# zxuno_v41.net
KiCad netlist of a schematic drawn in EAGLE
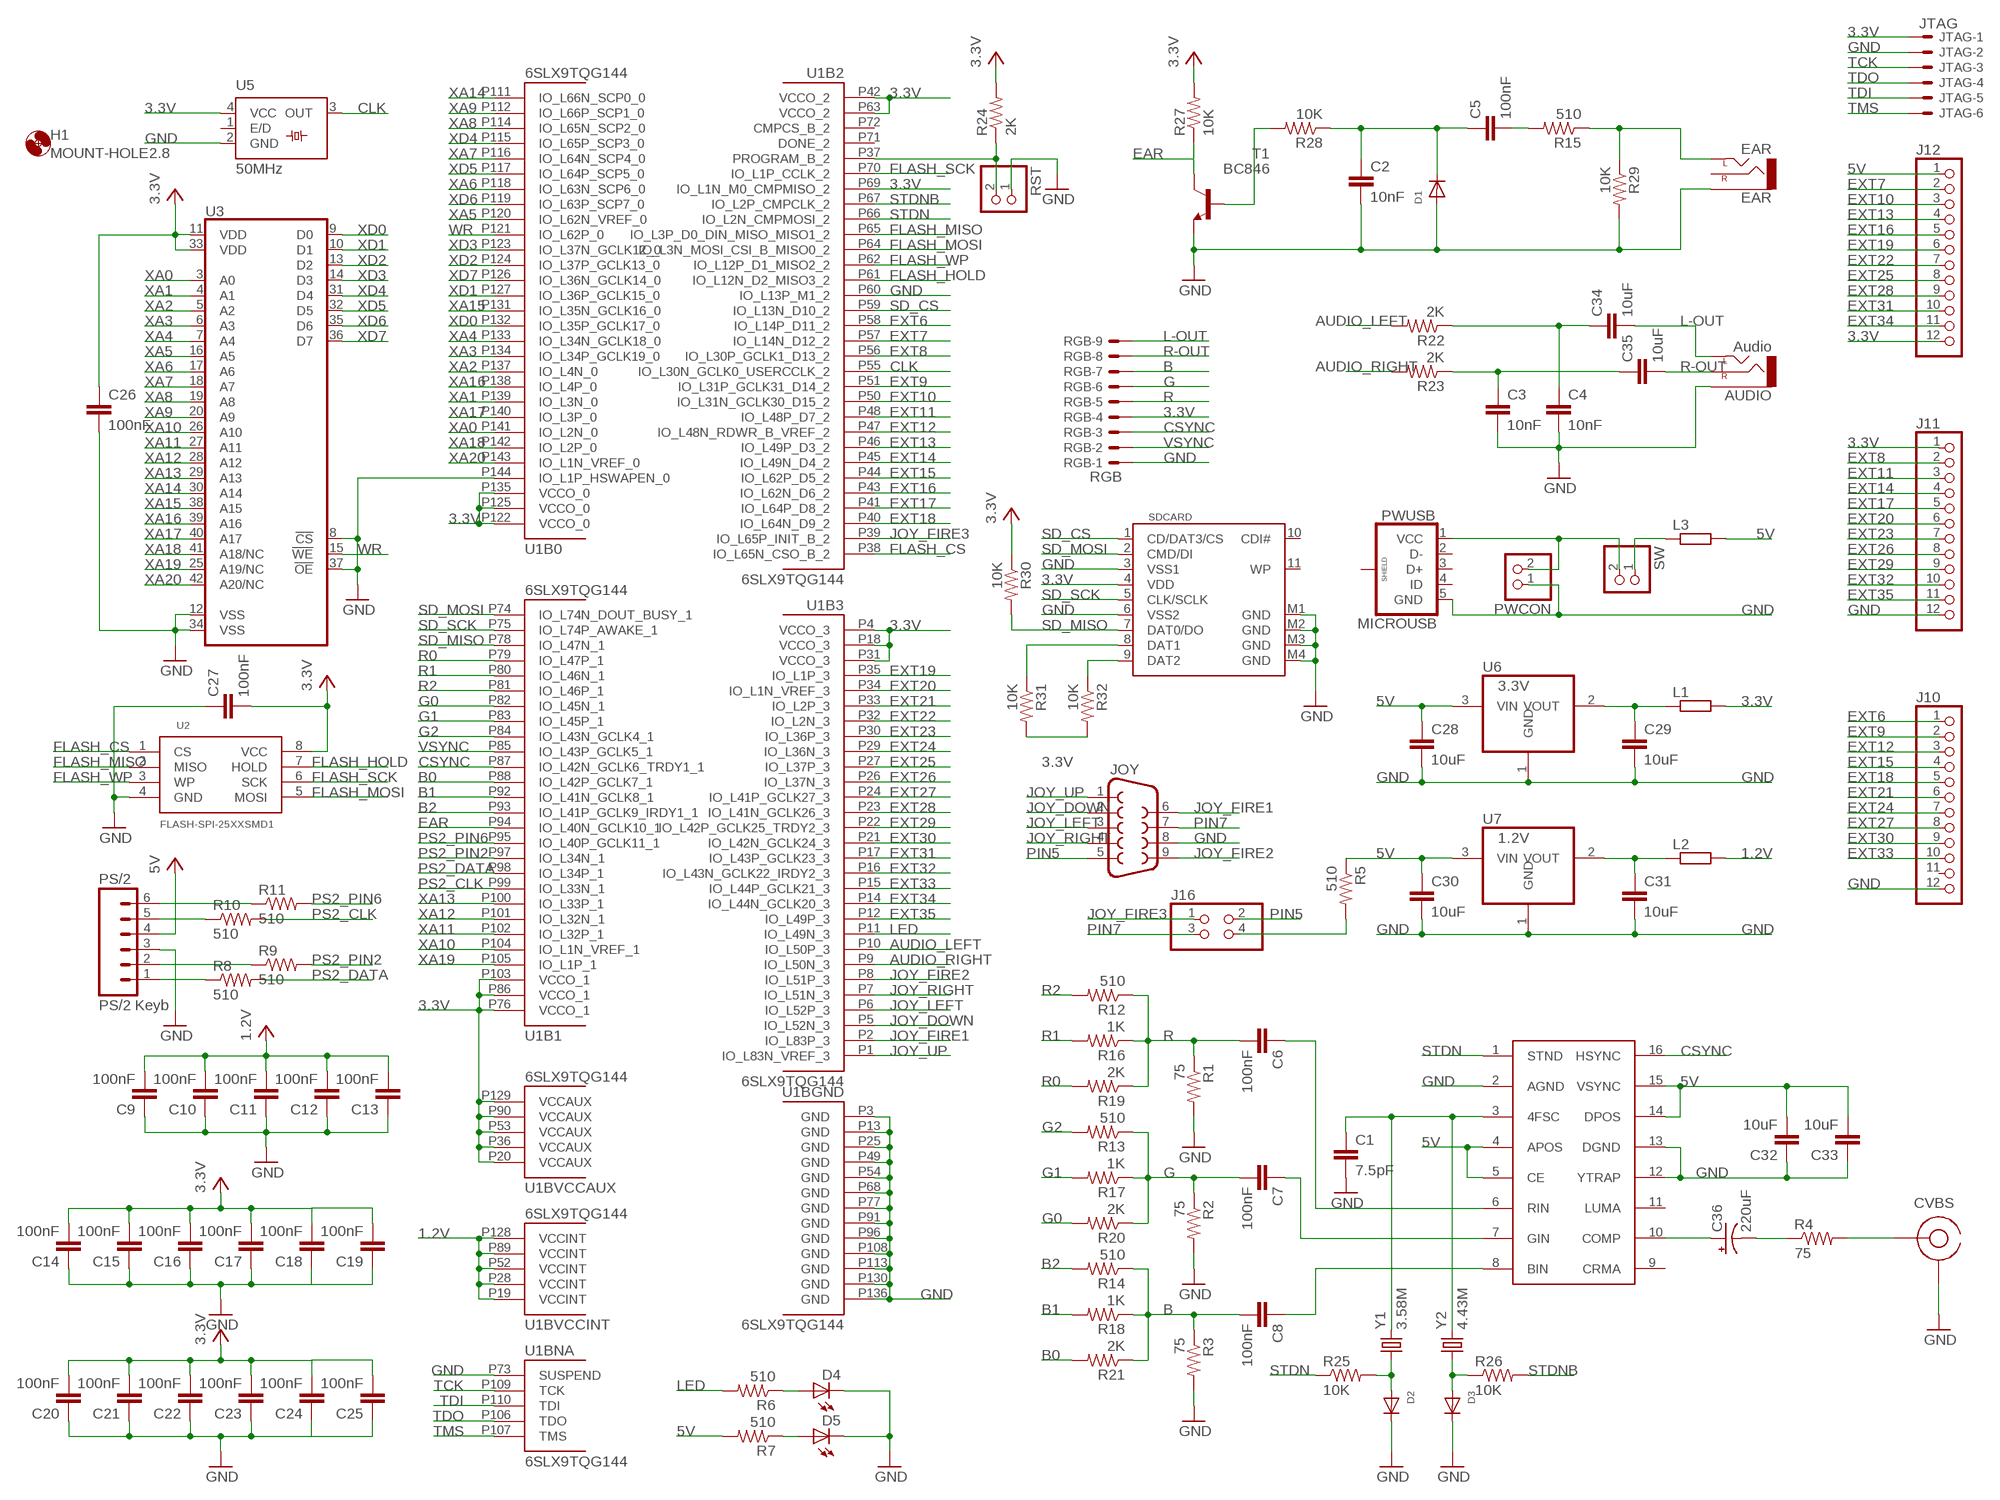
[diagram p0: schematic, sheet 1]

(export (version "E")
  (design (tool "Eeschema 10.0.6"))
  (components
    (comp (ref "AUDIO")
      (value "Audio")
      (footprint "eagle-import:AUDIO-JACK")
      (libsource (lib "eagle-import") (part "AUDIO-JACKPTH"))
    )
    (comp (ref "C1")
      (value "7.5pF")
      (footprint "eagle-import:C0805")
      (libsource (lib "eagle-import") (part "C-EUC0805"))
    )
    (comp (ref "C2")
      (value "10nF")
      (footprint "eagle-import:C0805")
      (libsource (lib "eagle-import") (part "C-EUC0805"))
    )
    (comp (ref "C3")
      (value "10nF")
      (footprint "eagle-import:C0805")
      (libsource (lib "eagle-import") (part "C-EUC0805"))
    )
    (comp (ref "C4")
      (value "10nF")
      (footprint "eagle-import:C0805")
      (libsource (lib "eagle-import") (part "C-EUC0805"))
    )
    (comp (ref "C5")
      (value "100nF")
      (footprint "eagle-import:C0603")
      (libsource (lib "eagle-import") (part "C-EUC0603"))
    )
    (comp (ref "C6")
      (value "100nF")
      (footprint "eagle-import:C0603")
      (libsource (lib "eagle-import") (part "C-EUC0603"))
    )
    (comp (ref "C7")
      (value "100nF")
      (footprint "eagle-import:C0603")
      (libsource (lib "eagle-import") (part "C-EUC0603"))
    )
    (comp (ref "C8")
      (value "100nF")
      (footprint "eagle-import:C0603")
      (libsource (lib "eagle-import") (part "C-EUC0603"))
    )
    (comp (ref "C9")
      (value "100nF")
      (footprint "eagle-import:C0603")
      (libsource (lib "eagle-import") (part "C-EUC0603"))
    )
    (comp (ref "C10")
      (value "100nF")
      (footprint "eagle-import:C0603")
      (libsource (lib "eagle-import") (part "C-EUC0603"))
    )
    (comp (ref "C11")
      (value "100nF")
      (footprint "eagle-import:C0603")
      (libsource (lib "eagle-import") (part "C-EUC0603"))
    )
    (comp (ref "C12")
      (value "100nF")
      (footprint "eagle-import:C0603")
      (libsource (lib "eagle-import") (part "C-EUC0603"))
    )
    (comp (ref "C13")
      (value "100nF")
      (footprint "eagle-import:C0603")
      (libsource (lib "eagle-import") (part "C-EUC0603"))
    )
    (comp (ref "C14")
      (value "100nF")
      (footprint "eagle-import:C0603")
      (libsource (lib "eagle-import") (part "C-EUC0603"))
    )
    (comp (ref "C15")
      (value "100nF")
      (footprint "eagle-import:C0603")
      (libsource (lib "eagle-import") (part "C-EUC0603"))
    )
    (comp (ref "C16")
      (value "100nF")
      (footprint "eagle-import:C0603")
      (libsource (lib "eagle-import") (part "C-EUC0603"))
    )
    (comp (ref "C17")
      (value "100nF")
      (footprint "eagle-import:C0603")
      (libsource (lib "eagle-import") (part "C-EUC0603"))
    )
    (comp (ref "C18")
      (value "100nF")
      (footprint "eagle-import:C0603")
      (libsource (lib "eagle-import") (part "C-EUC0603"))
    )
    (comp (ref "C19")
      (value "100nF")
      (footprint "eagle-import:C0603")
      (libsource (lib "eagle-import") (part "C-EUC0603"))
    )
    (comp (ref "C20")
      (value "100nF")
      (footprint "eagle-import:C0603")
      (libsource (lib "eagle-import") (part "C-EUC0603"))
    )
    (comp (ref "C21")
      (value "100nF")
      (footprint "eagle-import:C0603")
      (libsource (lib "eagle-import") (part "C-EUC0603"))
    )
    (comp (ref "C22")
      (value "100nF")
      (footprint "eagle-import:C0603")
      (libsource (lib "eagle-import") (part "C-EUC0603"))
    )
    (comp (ref "C23")
      (value "100nF")
      (footprint "eagle-import:C0603")
      (libsource (lib "eagle-import") (part "C-EUC0603"))
    )
    (comp (ref "C24")
      (value "100nF")
      (footprint "eagle-import:C0603")
      (libsource (lib "eagle-import") (part "C-EUC0603"))
    )
    (comp (ref "C25")
      (value "100nF")
      (footprint "eagle-import:C0603")
      (libsource (lib "eagle-import") (part "C-EUC0603"))
    )
    (comp (ref "C26")
      (value "100nF")
      (footprint "eagle-import:C0603")
      (libsource (lib "eagle-import") (part "C-EUC0603"))
    )
    (comp (ref "C27")
      (value "100nF")
      (footprint "eagle-import:C0603")
      (libsource (lib "eagle-import") (part "C-EUC0603"))
    )
    (comp (ref "C28")
      (value "10uF")
      (footprint "eagle-import:C0805")
      (libsource (lib "eagle-import") (part "C-EUC0805"))
    )
    (comp (ref "C29")
      (value "10uF")
      (footprint "eagle-import:C0805")
      (libsource (lib "eagle-import") (part "C-EUC0805"))
    )
    (comp (ref "C30")
      (value "10uF")
      (footprint "eagle-import:C0805")
      (libsource (lib "eagle-import") (part "C-EUC0805"))
    )
    (comp (ref "C31")
      (value "10uF")
      (footprint "eagle-import:C0805")
      (libsource (lib "eagle-import") (part "C-EUC0805"))
    )
    (comp (ref "C32")
      (value "10uF")
      (footprint "eagle-import:C0805")
      (libsource (lib "eagle-import") (part "C-EUC0805"))
    )
    (comp (ref "C33")
      (value "10uF")
      (footprint "eagle-import:C0805")
      (libsource (lib "eagle-import") (part "C-EUC0805"))
    )
    (comp (ref "C34")
      (value "10uF")
      (footprint "eagle-import:C0805")
      (libsource (lib "eagle-import") (part "C-EUC0805"))
    )
    (comp (ref "C35")
      (value "10uF")
      (footprint "eagle-import:C0805")
      (libsource (lib "eagle-import") (part "C-EUC0805"))
    )
    (comp (ref "C36")
      (value "220uF")
      (footprint "eagle-import:153CLV-0605")
      (libsource (lib "eagle-import") (part "CPOL-US153CLV-0605"))
    )
    (comp (ref "CVBS")
      (value "RCA")
      (footprint "eagle-import:RCA")
      (libsource (lib "eagle-import") (part "RCA"))
    )
    (comp (ref "D1")
      (value "DIODESOD-323F")
      (footprint "eagle-import:SOD-323F")
      (libsource (lib "eagle-import") (part "DIODESOD-323F"))
    )
    (comp (ref "D2")
      (value "DIODESOD-323F")
      (footprint "eagle-import:SOD-323F")
      (libsource (lib "eagle-import") (part "DIODESOD-323F"))
    )
    (comp (ref "D3")
      (value "DIODESOD-323F")
      (footprint "eagle-import:SOD-323F")
      (libsource (lib "eagle-import") (part "DIODESOD-323F"))
    )
    (comp (ref "D4")
      (value "LEDCHIP-LED0805")
      (footprint "eagle-import:CHIP-LED0805")
      (libsource (lib "eagle-import") (part "LEDCHIP-LED0805"))
    )
    (comp (ref "D5")
      (value "LEDCHIP-LED0805")
      (footprint "eagle-import:CHIP-LED0805")
      (libsource (lib "eagle-import") (part "LEDCHIP-LED0805"))
    )
    (comp (ref "EAR")
      (value "EAR")
      (footprint "eagle-import:AUDIO-JACK")
      (libsource (lib "eagle-import") (part "AUDIO-JACKPTH"))
    )
    (comp (ref "H1")
      (value "MOUNT-HOLE2.8")
      (footprint "eagle-import:2,8")
      (libsource (lib "eagle-import") (part "MOUNT-HOLE2.8"))
    )
    (comp (ref "J10")
      (value "PINHD-1X12")
      (footprint "eagle-import:1X12")
      (libsource (lib "eagle-import") (part "PINHD-1X12"))
    )
    (comp (ref "J11")
      (value "PINHD-1X12")
      (footprint "eagle-import:1X12")
      (libsource (lib "eagle-import") (part "PINHD-1X12"))
    )
    (comp (ref "J12")
      (value "PINHD-1X12")
      (footprint "eagle-import:1X12")
      (libsource (lib "eagle-import") (part "PINHD-1X12"))
    )
    (comp (ref "J16")
      (value "PINHD-2X2")
      (footprint "eagle-import:2X02")
      (libsource (lib "eagle-import") (part "PINHD-2X2"))
    )
    (comp (ref "JOY")
      (value "DB9MALE")
      (footprint "eagle-import:DB9_MALE")
      (libsource (lib "eagle-import") (part "DB9MALE"))
    )
    (comp (ref "JTAG")
      (value "JTAG")
      (footprint "eagle-import:53047-06")
      (fields (field (name "MPN") "53047-0610-C"))
      (libsource (lib "eagle-import") (part "53?-06047"))
    )
    (comp (ref "L1")
      (value "R-EU_M0805")
      (footprint "eagle-import:M0805")
      (libsource (lib "eagle-import") (part "R-EU_M0805"))
    )
    (comp (ref "L2")
      (value "R-EU_M0805")
      (footprint "eagle-import:M0805")
      (libsource (lib "eagle-import") (part "R-EU_M0805"))
    )
    (comp (ref "L3")
      (value "R-EU_M0805")
      (footprint "eagle-import:M0805")
      (libsource (lib "eagle-import") (part "R-EU_M0805"))
    )
    (comp (ref "PS/2")
      (value "PS/2 Keyb")
      (footprint "eagle-import:DINC_MIN_TM_6_1PRIMARY")
      (libsource (lib "eagle-import") (part "DINC_MIN_TM_6_1"))
    )
    (comp (ref "PWCON")
      (value "PINHD-1X2")
      (footprint "eagle-import:1X02")
      (libsource (lib "eagle-import") (part "PINHD-1X2"))
    )
    (comp (ref "PWUSB")
      (value "MICROUSB")
      (footprint "eagle-import:MICRO_USB_1PRIMARY")
      (libsource (lib "eagle-import") (part "MICROUSB"))
    )
    (comp (ref "R1")
      (value "75")
      (footprint "eagle-import:M0805")
      (libsource (lib "eagle-import") (part "R-US_M0805"))
    )
    (comp (ref "R2")
      (value "75")
      (footprint "eagle-import:M0805")
      (libsource (lib "eagle-import") (part "R-US_M0805"))
    )
    (comp (ref "R3")
      (value "75")
      (footprint "eagle-import:M0805")
      (libsource (lib "eagle-import") (part "R-US_M0805"))
    )
    (comp (ref "R4")
      (value "75")
      (footprint "eagle-import:M0805")
      (libsource (lib "eagle-import") (part "R-US_M0805"))
    )
    (comp (ref "R5")
      (value "510")
      (footprint "eagle-import:M0805")
      (libsource (lib "eagle-import") (part "R-US_M0805"))
    )
    (comp (ref "R6")
      (value "510")
      (footprint "eagle-import:M0805")
      (libsource (lib "eagle-import") (part "R-US_M0805"))
    )
    (comp (ref "R7")
      (value "510")
      (footprint "eagle-import:M0805")
      (libsource (lib "eagle-import") (part "R-US_M0805"))
    )
    (comp (ref "R8")
      (value "510")
      (footprint "eagle-import:M0805")
      (libsource (lib "eagle-import") (part "R-US_M0805"))
    )
    (comp (ref "R9")
      (value "510")
      (footprint "eagle-import:M0805")
      (libsource (lib "eagle-import") (part "R-US_M0805"))
    )
    (comp (ref "R10")
      (value "510")
      (footprint "eagle-import:M0805")
      (libsource (lib "eagle-import") (part "R-US_M0805"))
    )
    (comp (ref "R11")
      (value "510")
      (footprint "eagle-import:M0805")
      (libsource (lib "eagle-import") (part "R-US_M0805"))
    )
    (comp (ref "R12")
      (value "510")
      (footprint "eagle-import:M0805")
      (libsource (lib "eagle-import") (part "R-US_M0805"))
    )
    (comp (ref "R13")
      (value "510")
      (footprint "eagle-import:M0805")
      (libsource (lib "eagle-import") (part "R-US_M0805"))
    )
    (comp (ref "R14")
      (value "510")
      (footprint "eagle-import:M0805")
      (libsource (lib "eagle-import") (part "R-US_M0805"))
    )
    (comp (ref "R15")
      (value "510")
      (footprint "eagle-import:M0805")
      (libsource (lib "eagle-import") (part "R-US_M0805"))
    )
    (comp (ref "R16")
      (value "1K")
      (footprint "eagle-import:M0805")
      (libsource (lib "eagle-import") (part "R-US_M0805"))
    )
    (comp (ref "R17")
      (value "1K")
      (footprint "eagle-import:M0805")
      (libsource (lib "eagle-import") (part "R-US_M0805"))
    )
    (comp (ref "R18")
      (value "1K")
      (footprint "eagle-import:M0805")
      (libsource (lib "eagle-import") (part "R-US_M0805"))
    )
    (comp (ref "R19")
      (value "2K")
      (footprint "eagle-import:M0805")
      (libsource (lib "eagle-import") (part "R-US_M0805"))
    )
    (comp (ref "R20")
      (value "2K")
      (footprint "eagle-import:M0805")
      (libsource (lib "eagle-import") (part "R-US_M0805"))
    )
    (comp (ref "R21")
      (value "2K")
      (footprint "eagle-import:M0805")
      (libsource (lib "eagle-import") (part "R-US_M0805"))
    )
    (comp (ref "R22")
      (value "2K")
      (footprint "eagle-import:M0805")
      (libsource (lib "eagle-import") (part "R-US_M0805"))
    )
    (comp (ref "R23")
      (value "2K")
      (footprint "eagle-import:M0805")
      (libsource (lib "eagle-import") (part "R-US_M0805"))
    )
    (comp (ref "R24")
      (value "2K")
      (footprint "eagle-import:M0805")
      (libsource (lib "eagle-import") (part "R-US_M0805"))
    )
    (comp (ref "R25")
      (value "10K")
      (footprint "eagle-import:M0805")
      (libsource (lib "eagle-import") (part "R-US_M0805"))
    )
    (comp (ref "R26")
      (value "10K")
      (footprint "eagle-import:M0805")
      (libsource (lib "eagle-import") (part "R-US_M0805"))
    )
    (comp (ref "R27")
      (value "10K")
      (footprint "eagle-import:M0805")
      (libsource (lib "eagle-import") (part "R-US_M0805"))
    )
    (comp (ref "R28")
      (value "10K")
      (footprint "eagle-import:M0805")
      (libsource (lib "eagle-import") (part "R-US_M0805"))
    )
    (comp (ref "R29")
      (value "10K")
      (footprint "eagle-import:M0805")
      (libsource (lib "eagle-import") (part "R-US_M0805"))
    )
    (comp (ref "R30")
      (value "10K")
      (footprint "eagle-import:M0805")
      (libsource (lib "eagle-import") (part "R-US_M0805"))
    )
    (comp (ref "R31")
      (value "10K")
      (footprint "eagle-import:M0805")
      (libsource (lib "eagle-import") (part "R-US_M0805"))
    )
    (comp (ref "R32")
      (value "10K")
      (footprint "eagle-import:M0805")
      (libsource (lib "eagle-import") (part "R-US_M0805"))
    )
    (comp (ref "RGB")
      (value "RGB")
      (footprint "eagle-import:53048-09")
      (fields (field (name "MPN") "53048-0910"))
      (libsource (lib "eagle-import") (part "53?-09048"))
    )
    (comp (ref "RST")
      (value "PINHD-1X2")
      (footprint "eagle-import:1X02")
      (libsource (lib "eagle-import") (part "PINHD-1X2"))
    )
    (comp (ref "SDCARD")
      (value "SDCARD")
      (footprint "eagle-import:SDCMF-10915W010")
      (libsource (lib "eagle-import") (part "SDCARD"))
    )
    (comp (ref "SW")
      (value "PINHD-1X2")
      (footprint "eagle-import:1X02")
      (libsource (lib "eagle-import") (part "PINHD-1X2"))
    )
    (comp (ref "T1")
      (value "BC846")
      (footprint "eagle-import:SOT23")
      (libsource (lib "eagle-import") (part "BC846"))
    )
    (comp (ref "U1")
      (value "6SLX9TQG144")
      (footprint "eagle-import:TQ144")
      (libsource (lib "eagle-import") (part "6SLX9TQG144"))
    )
    (comp (ref "U2")
      (value "FLASH-SPI-25XXSMD1")
      (footprint "eagle-import:SO08-EIAJ")
      (libsource (lib "eagle-import") (part "FLASH-SPI-25XXSMD1"))
    )
    (comp (ref "U3")
      (value "ISSI_SRAM_8BIT")
      (footprint "eagle-import:TSOP44-II")
      (libsource (lib "eagle-import") (part "ISSI_SRAM_8BIT"))
    )
    (comp (ref "U4")
      (value "AD724")
      (footprint "eagle-import:SO16W")
      (libsource (lib "eagle-import") (part "AD725"))
    )
    (comp (ref "U5")
      (value "50MHz")
      (footprint "eagle-import:SM_OSC_1PRIMARY")
      (libsource (lib "eagle-import") (part "SM_OSC_1"))
    )
    (comp (ref "U6")
      (value "3.3V")
      (footprint "eagle-import:SOT223")
      (fields (field (name "MPN") "REG1117"))
      (libsource (lib "eagle-import") (part "REG1117"))
    )
    (comp (ref "U7")
      (value "1.2V")
      (footprint "eagle-import:SOT223")
      (fields (field (name "MPN") "REG1117"))
      (libsource (lib "eagle-import") (part "REG1117"))
    )
    (comp (ref "Y1")
      (value "3.58M")
      (footprint "eagle-import:HC49UP")
      (libsource (lib "eagle-import") (part "CRYSTALHC49UP"))
    )
    (comp (ref "Y2")
      (value "4.43M")
      (footprint "eagle-import:HC49UP")
      (libsource (lib "eagle-import") (part "CRYSTALHC49UP"))
    )
  )
  (nets
    (net (code "1") (name "/AUDIO_LEFT") (class "Default")
      (node (ref "R22") (pin "2") (pinfunction "2_2") (pintype "passive"))
      (node (ref "U1") (pin "P10") (pinfunction "IO_L50P_3_P10") (pintype "bidirectional"))
    )
    (net (code "2") (name "/AUDIO_RIGHT") (class "Default")
      (node (ref "R23") (pin "2") (pinfunction "2_2") (pintype "passive"))
      (node (ref "U1") (pin "P9") (pinfunction "IO_L50N_3_P9") (pintype "bidirectional"))
    )
    (net (code "3") (name "/B") (class "Default")
      (node (ref "C8") (pin "2") (pinfunction "2_2") (pintype "passive"))
      (node (ref "R14") (pin "1") (pinfunction "1_1") (pintype "passive"))
      (node (ref "R18") (pin "1") (pinfunction "1_1") (pintype "passive"))
      (node (ref "R21") (pin "1") (pinfunction "1_1") (pintype "passive"))
      (node (ref "R3") (pin "1") (pinfunction "1_1") (pintype "passive"))
      (node (ref "RGB") (pin "7") (pinfunction "S_7") (pintype "passive"))
    )
    (net (code "4") (name "/B0") (class "Default")
      (node (ref "R21") (pin "2") (pinfunction "2_2") (pintype "passive"))
      (node (ref "U1") (pin "P88") (pinfunction "IO_L42P_GCLK7_1_P88") (pintype "bidirectional"))
    )
    (net (code "5") (name "/B1") (class "Default")
      (node (ref "R18") (pin "2") (pinfunction "2_2") (pintype "passive"))
      (node (ref "U1") (pin "P92") (pinfunction "IO_L41N_GCLK8_1_P92") (pintype "bidirectional"))
    )
    (net (code "6") (name "/B2") (class "Default")
      (node (ref "R14") (pin "2") (pinfunction "2_2") (pintype "passive"))
      (node (ref "U1") (pin "P93") (pinfunction "IO_L41P_GCLK9_IRDY1_1_P93") (pintype "bidirectional"))
    )
    (net (code "7") (name "/CLK") (class "Default")
      (node (ref "U1") (pin "P55") (pinfunction "IO_L30N_GCLK0_USERCCLK_2_P55") (pintype "bidirectional"))
      (node (ref "U5") (pin "3") (pinfunction "OUT_3") (pintype "output"))
    )
    (net (code "8") (name "/CSYNC") (class "Default")
      (node (ref "RGB") (pin "3") (pinfunction "S_3") (pintype "passive"))
      (node (ref "U1") (pin "P87") (pinfunction "IO_L42N_GCLK6_TRDY1_1_P87") (pintype "bidirectional"))
      (node (ref "U4") (pin "16") (pinfunction "HSYNC_16") (pintype "bidirectional"))
    )
    (net (code "9") (name "/EAR") (class "Default")
      (node (ref "R27") (pin "1") (pinfunction "1_1") (pintype "passive"))
      (node (ref "T1") (pin "3") (pinfunction "C_3") (pintype "passive"))
      (node (ref "U1") (pin "P94") (pinfunction "IO_L40N_GCLK10_1_P94") (pintype "bidirectional"))
    )
    (net (code "10") (name "/EXT6") (class "Default")
      (node (ref "J10") (pin "1") (pinfunction "1_1") (pintype "passive"))
      (node (ref "U1") (pin "P58") (pinfunction "IO_L14P_D11_2_P58") (pintype "bidirectional"))
    )
    (net (code "11") (name "/EXT7") (class "Default")
      (node (ref "J12") (pin "2") (pinfunction "2_2") (pintype "passive"))
      (node (ref "U1") (pin "P57") (pinfunction "IO_L14N_D12_2_P57") (pintype "bidirectional"))
    )
    (net (code "12") (name "/EXT8") (class "Default")
      (node (ref "J11") (pin "2") (pinfunction "2_2") (pintype "passive"))
      (node (ref "U1") (pin "P56") (pinfunction "IO_L30P_GCLK1_D13_2_P56") (pintype "bidirectional"))
    )
    (net (code "13") (name "/EXT9") (class "Default")
      (node (ref "J10") (pin "2") (pinfunction "2_2") (pintype "passive"))
      (node (ref "U1") (pin "P51") (pinfunction "IO_L31P_GCLK31_D14_2_P51") (pintype "bidirectional"))
    )
    (net (code "14") (name "/EXT10") (class "Default")
      (node (ref "J12") (pin "3") (pinfunction "3_3") (pintype "passive"))
      (node (ref "U1") (pin "P50") (pinfunction "IO_L31N_GCLK30_D15_2_P50") (pintype "bidirectional"))
    )
    (net (code "15") (name "/EXT11") (class "Default")
      (node (ref "J11") (pin "3") (pinfunction "3_3") (pintype "passive"))
      (node (ref "U1") (pin "P48") (pinfunction "IO_L48P_D7_2_P48") (pintype "bidirectional"))
    )
    (net (code "16") (name "/EXT12") (class "Default")
      (node (ref "J10") (pin "3") (pinfunction "3_3") (pintype "passive"))
      (node (ref "U1") (pin "P47") (pinfunction "IO_L48N_RDWR_B_VREF_2_P47") (pintype "bidirectional"))
    )
    (net (code "17") (name "/EXT13") (class "Default")
      (node (ref "J12") (pin "4") (pinfunction "4_4") (pintype "passive"))
      (node (ref "U1") (pin "P46") (pinfunction "IO_L49P_D3_2_P46") (pintype "bidirectional"))
    )
    (net (code "18") (name "/EXT14") (class "Default")
      (node (ref "J11") (pin "4") (pinfunction "4_4") (pintype "passive"))
      (node (ref "U1") (pin "P45") (pinfunction "IO_L49N_D4_2_P45") (pintype "bidirectional"))
    )
    (net (code "19") (name "/EXT15") (class "Default")
      (node (ref "J10") (pin "4") (pinfunction "4_4") (pintype "passive"))
      (node (ref "U1") (pin "P44") (pinfunction "IO_L62P_D5_2_P44") (pintype "bidirectional"))
    )
    (net (code "20") (name "/EXT16") (class "Default")
      (node (ref "J12") (pin "5") (pinfunction "5_5") (pintype "passive"))
      (node (ref "U1") (pin "P43") (pinfunction "IO_L62N_D6_2_P43") (pintype "bidirectional"))
    )
    (net (code "21") (name "/EXT17") (class "Default")
      (node (ref "J11") (pin "5") (pinfunction "5_5") (pintype "passive"))
      (node (ref "U1") (pin "P41") (pinfunction "IO_L64P_D8_2_P41") (pintype "bidirectional"))
    )
    (net (code "22") (name "/EXT18") (class "Default")
      (node (ref "J10") (pin "5") (pinfunction "5_5") (pintype "passive"))
      (node (ref "U1") (pin "P40") (pinfunction "IO_L64N_D9_2_P40") (pintype "bidirectional"))
    )
    (net (code "23") (name "/EXT19") (class "Default")
      (node (ref "J12") (pin "6") (pinfunction "6_6") (pintype "passive"))
      (node (ref "U1") (pin "P35") (pinfunction "IO_L1P_3_P35") (pintype "bidirectional"))
    )
    (net (code "24") (name "/EXT20") (class "Default")
      (node (ref "J11") (pin "6") (pinfunction "6_6") (pintype "passive"))
      (node (ref "U1") (pin "P34") (pinfunction "IO_L1N_VREF_3_P34") (pintype "bidirectional"))
    )
    (net (code "25") (name "/EXT21") (class "Default")
      (node (ref "J10") (pin "6") (pinfunction "6_6") (pintype "passive"))
      (node (ref "U1") (pin "P33") (pinfunction "IO_L2P_3_P33") (pintype "bidirectional"))
    )
    (net (code "26") (name "/EXT22") (class "Default")
      (node (ref "J12") (pin "7") (pinfunction "7_7") (pintype "passive"))
      (node (ref "U1") (pin "P32") (pinfunction "IO_L2N_3_P32") (pintype "bidirectional"))
    )
    (net (code "27") (name "/EXT23") (class "Default")
      (node (ref "J11") (pin "7") (pinfunction "7_7") (pintype "passive"))
      (node (ref "U1") (pin "P30") (pinfunction "IO_L36P_3_P30") (pintype "bidirectional"))
    )
    (net (code "28") (name "/EXT24") (class "Default")
      (node (ref "J10") (pin "7") (pinfunction "7_7") (pintype "passive"))
      (node (ref "U1") (pin "P29") (pinfunction "IO_L36N_3_P29") (pintype "bidirectional"))
    )
    (net (code "29") (name "/EXT25") (class "Default")
      (node (ref "J12") (pin "8") (pinfunction "8_8") (pintype "passive"))
      (node (ref "U1") (pin "P27") (pinfunction "IO_L37P_3_P27") (pintype "bidirectional"))
    )
    (net (code "30") (name "/EXT26") (class "Default")
      (node (ref "J11") (pin "8") (pinfunction "8_8") (pintype "passive"))
      (node (ref "U1") (pin "P26") (pinfunction "IO_L37N_3_P26") (pintype "bidirectional"))
    )
    (net (code "31") (name "/EXT27") (class "Default")
      (node (ref "J10") (pin "8") (pinfunction "8_8") (pintype "passive"))
      (node (ref "U1") (pin "P24") (pinfunction "IO_L41P_GCLK27_3_P24") (pintype "bidirectional"))
    )
    (net (code "32") (name "/EXT28") (class "Default")
      (node (ref "J12") (pin "9") (pinfunction "9_9") (pintype "passive"))
      (node (ref "U1") (pin "P23") (pinfunction "IO_L41N_GCLK26_3_P23") (pintype "bidirectional"))
    )
    (net (code "33") (name "/EXT29") (class "Default")
      (node (ref "J11") (pin "9") (pinfunction "9_9") (pintype "passive"))
      (node (ref "U1") (pin "P22") (pinfunction "IO_L42P_GCLK25_TRDY2_3_P22") (pintype "bidirectional"))
    )
    (net (code "34") (name "/EXT30") (class "Default")
      (node (ref "J10") (pin "9") (pinfunction "9_9") (pintype "passive"))
      (node (ref "U1") (pin "P21") (pinfunction "IO_L42N_GCLK24_3_P21") (pintype "bidirectional"))
    )
    (net (code "35") (name "/EXT31") (class "Default")
      (node (ref "J12") (pin "10") (pinfunction "10_10") (pintype "passive"))
      (node (ref "U1") (pin "P17") (pinfunction "IO_L43P_GCLK23_3_P17") (pintype "bidirectional"))
    )
    (net (code "36") (name "/EXT32") (class "Default")
      (node (ref "J11") (pin "10") (pinfunction "10_10") (pintype "passive"))
      (node (ref "U1") (pin "P16") (pinfunction "IO_L43N_GCLK22_IRDY2_3_P16") (pintype "bidirectional"))
    )
    (net (code "37") (name "/EXT33") (class "Default")
      (node (ref "J10") (pin "10") (pinfunction "10_10") (pintype "passive"))
      (node (ref "U1") (pin "P15") (pinfunction "IO_L44P_GCLK21_3_P15") (pintype "bidirectional"))
    )
    (net (code "38") (name "/EXT34") (class "Default")
      (node (ref "J12") (pin "11") (pinfunction "11_11") (pintype "passive"))
      (node (ref "U1") (pin "P14") (pinfunction "IO_L44N_GCLK20_3_P14") (pintype "bidirectional"))
    )
    (net (code "39") (name "/EXT35") (class "Default")
      (node (ref "J11") (pin "11") (pinfunction "11_11") (pintype "passive"))
      (node (ref "U1") (pin "P12") (pinfunction "IO_L49P_3_P12") (pintype "bidirectional"))
    )
    (net (code "40") (name "/FLASH_CS") (class "Default")
      (node (ref "U1") (pin "P38") (pinfunction "IO_L65N_CSO_B_2_P38") (pintype "bidirectional"))
      (node (ref "U2") (pin "1") (pinfunction "CS_1") (pintype "bidirectional"))
    )
    (net (code "41") (name "/FLASH_HOLD") (class "Default")
      (node (ref "U1") (pin "P61") (pinfunction "IO_L12N_D2_MISO3_2_P61") (pintype "bidirectional"))
      (node (ref "U2") (pin "7") (pinfunction "HOLD_7") (pintype "bidirectional"))
    )
    (net (code "42") (name "/FLASH_MISO") (class "Default")
      (node (ref "U1") (pin "P65") (pinfunction "IO_L3P_D0_DIN_MISO_MISO1_2_P65") (pintype "bidirectional"))
      (node (ref "U2") (pin "2") (pinfunction "MISO_2") (pintype "bidirectional"))
    )
    (net (code "43") (name "/FLASH_MOSI") (class "Default")
      (node (ref "U1") (pin "P64") (pinfunction "IO_L3N_MOSI_CSI_B_MISO0_2_P64") (pintype "bidirectional"))
      (node (ref "U2") (pin "5") (pinfunction "MOSI_5") (pintype "bidirectional"))
    )
    (net (code "44") (name "/FLASH_SCK") (class "Default")
      (node (ref "U1") (pin "P70") (pinfunction "IO_L1P_CCLK_2_P70") (pintype "bidirectional"))
      (node (ref "U2") (pin "6") (pinfunction "SCK_6") (pintype "bidirectional"))
    )
    (net (code "45") (name "/FLASH_WP") (class "Default")
      (node (ref "U1") (pin "P62") (pinfunction "IO_L12P_D1_MISO2_2_P62") (pintype "bidirectional"))
      (node (ref "U2") (pin "3") (pinfunction "WP_3") (pintype "bidirectional"))
    )
    (net (code "46") (name "/G") (class "Default")
      (node (ref "C7") (pin "2") (pinfunction "2_2") (pintype "passive"))
      (node (ref "R13") (pin "1") (pinfunction "1_1") (pintype "passive"))
      (node (ref "R17") (pin "1") (pinfunction "1_1") (pintype "passive"))
      (node (ref "R2") (pin "1") (pinfunction "1_1") (pintype "passive"))
      (node (ref "R20") (pin "1") (pinfunction "1_1") (pintype "passive"))
      (node (ref "RGB") (pin "6") (pinfunction "S_6") (pintype "passive"))
    )
    (net (code "47") (name "/G0") (class "Default")
      (node (ref "R20") (pin "2") (pinfunction "2_2") (pintype "passive"))
      (node (ref "U1") (pin "P82") (pinfunction "IO_L45N_1_P82") (pintype "bidirectional"))
    )
    (net (code "48") (name "/G1") (class "Default")
      (node (ref "R17") (pin "2") (pinfunction "2_2") (pintype "passive"))
      (node (ref "U1") (pin "P83") (pinfunction "IO_L45P_1_P83") (pintype "bidirectional"))
    )
    (net (code "49") (name "/G2") (class "Default")
      (node (ref "R13") (pin "2") (pinfunction "2_2") (pintype "passive"))
      (node (ref "U1") (pin "P84") (pinfunction "IO_L43N_GCLK4_1_P84") (pintype "bidirectional"))
    )
    (net (code "50") (name "/JOY_DOWN") (class "Default")
      (node (ref "JOY") (pin "2") (pinfunction "2_2") (pintype "passive"))
      (node (ref "U1") (pin "P5") (pinfunction "IO_L52N_3_P5") (pintype "bidirectional"))
    )
    (net (code "51") (name "/JOY_FIRE1") (class "Default")
      (node (ref "JOY") (pin "6") (pinfunction "6_6") (pintype "passive"))
      (node (ref "U1") (pin "P2") (pinfunction "IO_L83P_3_P2") (pintype "bidirectional"))
    )
    (net (code "52") (name "/JOY_FIRE2") (class "Default")
      (node (ref "JOY") (pin "9") (pinfunction "9_9") (pintype "passive"))
      (node (ref "U1") (pin "P8") (pinfunction "IO_L51P_3_P8") (pintype "bidirectional"))
    )
    (net (code "53") (name "/JOY_FIRE3") (class "Default")
      (node (ref "J16") (pin "1") (pinfunction "1_1") (pintype "passive"))
      (node (ref "U1") (pin "P39") (pinfunction "IO_L65P_INIT_B_2_P39") (pintype "bidirectional"))
    )
    (net (code "54") (name "/JOY_LEFT") (class "Default")
      (node (ref "JOY") (pin "3") (pinfunction "3_3") (pintype "passive"))
      (node (ref "U1") (pin "P6") (pinfunction "IO_L52P_3_P6") (pintype "bidirectional"))
    )
    (net (code "55") (name "/JOY_RIGHT") (class "Default")
      (node (ref "JOY") (pin "4") (pinfunction "4_4") (pintype "passive"))
      (node (ref "U1") (pin "P7") (pinfunction "IO_L51N_3_P7") (pintype "bidirectional"))
    )
    (net (code "56") (name "/JOY_UP") (class "Default")
      (node (ref "JOY") (pin "1") (pinfunction "1_1") (pintype "passive"))
      (node (ref "U1") (pin "P1") (pinfunction "IO_L83N_VREF_3_P1") (pintype "bidirectional"))
    )
    (net (code "57") (name "/L-OUT") (class "Default")
      (node (ref "AUDIO") (pin "TIP") (pinfunction "LEFT_TIP") (pintype "bidirectional"))
      (node (ref "C34") (pin "2") (pinfunction "2_2") (pintype "passive"))
      (node (ref "RGB") (pin "9") (pinfunction "S_9") (pintype "passive"))
    )
    (net (code "58") (name "/LED") (class "Default")
      (node (ref "R6") (pin "2") (pinfunction "2_2") (pintype "passive"))
      (node (ref "U1") (pin "P11") (pinfunction "IO_L49N_3_P11") (pintype "bidirectional"))
    )
    (net (code "59") (name "/PIN5") (class "Default")
      (node (ref "J16") (pin "2") (pinfunction "2_2") (pintype "passive"))
      (node (ref "JOY") (pin "5") (pinfunction "5_5") (pintype "passive"))
    )
    (net (code "60") (name "/PIN7") (class "Default")
      (node (ref "J16") (pin "3") (pinfunction "3_3") (pintype "passive"))
      (node (ref "JOY") (pin "7") (pinfunction "7_7") (pintype "passive"))
    )
    (net (code "61") (name "/PS2_CLK") (class "Default")
      (node (ref "R10") (pin "2") (pinfunction "2_2") (pintype "passive"))
      (node (ref "U1") (pin "P99") (pinfunction "IO_L33N_1_P99") (pintype "bidirectional"))
    )
    (net (code "62") (name "/PS2_DATA") (class "Default")
      (node (ref "R8") (pin "2") (pinfunction "2_2") (pintype "passive"))
      (node (ref "U1") (pin "P98") (pinfunction "IO_L34P_1_P98") (pintype "bidirectional"))
    )
    (net (code "63") (name "/PS2_PIN2") (class "Default")
      (node (ref "R9") (pin "2") (pinfunction "2_2") (pintype "passive"))
      (node (ref "U1") (pin "P97") (pinfunction "IO_L34N_1_P97") (pintype "bidirectional"))
    )
    (net (code "64") (name "/PS2_PIN6") (class "Default")
      (node (ref "R11") (pin "2") (pinfunction "2_2") (pintype "passive"))
      (node (ref "U1") (pin "P95") (pinfunction "IO_L40P_GCLK11_1_P95") (pintype "bidirectional"))
    )
    (net (code "65") (name "/R") (class "Default")
      (node (ref "C6") (pin "2") (pinfunction "2_2") (pintype "passive"))
      (node (ref "R1") (pin "1") (pinfunction "1_1") (pintype "passive"))
      (node (ref "R12") (pin "1") (pinfunction "1_1") (pintype "passive"))
      (node (ref "R16") (pin "1") (pinfunction "1_1") (pintype "passive"))
      (node (ref "R19") (pin "1") (pinfunction "1_1") (pintype "passive"))
      (node (ref "RGB") (pin "5") (pinfunction "S_5") (pintype "passive"))
    )
    (net (code "66") (name "/R-OUT") (class "Default")
      (node (ref "AUDIO") (pin "RING") (pinfunction "RIGHT_RING") (pintype "bidirectional"))
      (node (ref "C35") (pin "2") (pinfunction "2_2") (pintype "passive"))
      (node (ref "RGB") (pin "8") (pinfunction "S_8") (pintype "passive"))
    )
    (net (code "67") (name "/R0") (class "Default")
      (node (ref "R19") (pin "2") (pinfunction "2_2") (pintype "passive"))
      (node (ref "U1") (pin "P79") (pinfunction "IO_L47P_1_P79") (pintype "bidirectional"))
    )
    (net (code "68") (name "/R1") (class "Default")
      (node (ref "R16") (pin "2") (pinfunction "2_2") (pintype "passive"))
      (node (ref "U1") (pin "P80") (pinfunction "IO_L46N_1_P80") (pintype "bidirectional"))
    )
    (net (code "69") (name "/R2") (class "Default")
      (node (ref "R12") (pin "2") (pinfunction "2_2") (pintype "passive"))
      (node (ref "U1") (pin "P81") (pinfunction "IO_L46P_1_P81") (pintype "bidirectional"))
    )
    (net (code "70") (name "/SD_CS") (class "Default")
      (node (ref "SDCARD") (pin "1") (pinfunction "CD/DAT3/CS_1") (pintype "bidirectional"))
      (node (ref "U1") (pin "P59") (pinfunction "IO_L13N_D10_2_P59") (pintype "bidirectional"))
    )
    (net (code "71") (name "/SD_MISO") (class "Default")
      (node (ref "R30") (pin "2") (pinfunction "2_2") (pintype "passive"))
      (node (ref "SDCARD") (pin "7") (pinfunction "DAT0/DO_7") (pintype "bidirectional"))
      (node (ref "U1") (pin "P78") (pinfunction "IO_L47N_1_P78") (pintype "bidirectional"))
    )
    (net (code "72") (name "/SD_MOSI") (class "Default")
      (node (ref "SDCARD") (pin "2") (pinfunction "CMD/DI_2") (pintype "bidirectional"))
      (node (ref "U1") (pin "P74") (pinfunction "IO_L74N_DOUT_BUSY_1_P74") (pintype "bidirectional"))
    )
    (net (code "73") (name "/SD_SCK") (class "Default")
      (node (ref "SDCARD") (pin "5") (pinfunction "CLK/SCLK_5") (pintype "bidirectional"))
      (node (ref "U1") (pin "P75") (pinfunction "IO_L74P_AWAKE_1_P75") (pintype "bidirectional"))
    )
    (net (code "74") (name "/STDN") (class "Default")
      (node (ref "R25") (pin "1") (pinfunction "1_1") (pintype "passive"))
      (node (ref "U1") (pin "P66") (pinfunction "IO_L2N_CMPMOSI_2_P66") (pintype "bidirectional"))
      (node (ref "U4") (pin "1") (pinfunction "STND_1") (pintype "bidirectional"))
    )
    (net (code "75") (name "/STDNB") (class "Default")
      (node (ref "R26") (pin "2") (pinfunction "2_2") (pintype "passive"))
      (node (ref "U1") (pin "P67") (pinfunction "IO_L2P_CMPCLK_2_P67") (pintype "bidirectional"))
    )
    (net (code "76") (name "/TCK") (class "Default")
      (node (ref "JTAG") (pin "3") (pinfunction "S_3") (pintype "passive"))
      (node (ref "U1") (pin "P109") (pinfunction "TCK_P109") (pintype "input"))
    )
    (net (code "77") (name "/TDI") (class "Default")
      (node (ref "JTAG") (pin "5") (pinfunction "S_5") (pintype "passive"))
      (node (ref "U1") (pin "P110") (pinfunction "TDI_P110") (pintype "input"))
    )
    (net (code "78") (name "/TDO") (class "Default")
      (node (ref "JTAG") (pin "4") (pinfunction "S_4") (pintype "passive"))
      (node (ref "U1") (pin "P106") (pinfunction "TDO_P106") (pintype "output"))
    )
    (net (code "79") (name "/TMS") (class "Default")
      (node (ref "JTAG") (pin "6") (pinfunction "S_6") (pintype "passive"))
      (node (ref "U1") (pin "P107") (pinfunction "TMS_P107") (pintype "input"))
    )
    (net (code "80") (name "/VSYNC") (class "Default")
      (node (ref "RGB") (pin "2") (pinfunction "S_2") (pintype "passive"))
      (node (ref "U1") (pin "P85") (pinfunction "IO_L43P_GCLK5_1_P85") (pintype "bidirectional"))
    )
    (net (code "81") (name "/WR") (class "Default")
      (node (ref "U1") (pin "P121") (pinfunction "IO_L62P_0_P121") (pintype "bidirectional"))
      (node (ref "U3") (pin "15") (pinfunction "~{WE}_15") (pintype "input"))
    )
    (net (code "82") (name "/XA0") (class "Default")
      (node (ref "U1") (pin "P141") (pinfunction "IO_L2N_0_P141") (pintype "bidirectional"))
      (node (ref "U3") (pin "3") (pinfunction "A0_3") (pintype "input"))
    )
    (net (code "83") (name "/XA1") (class "Default")
      (node (ref "U1") (pin "P139") (pinfunction "IO_L3N_0_P139") (pintype "bidirectional"))
      (node (ref "U3") (pin "4") (pinfunction "A1_4") (pintype "input"))
    )
    (net (code "84") (name "/XA2") (class "Default")
      (node (ref "U1") (pin "P137") (pinfunction "IO_L4N_0_P137") (pintype "bidirectional"))
      (node (ref "U3") (pin "5") (pinfunction "A2_5") (pintype "input"))
    )
    (net (code "85") (name "/XA3") (class "Default")
      (node (ref "U1") (pin "P134") (pinfunction "IO_L34P_GCLK19_0_P134") (pintype "bidirectional"))
      (node (ref "U3") (pin "6") (pinfunction "A3_6") (pintype "input"))
    )
    (net (code "86") (name "/XA4") (class "Default")
      (node (ref "U1") (pin "P133") (pinfunction "IO_L34N_GCLK18_0_P133") (pintype "bidirectional"))
      (node (ref "U3") (pin "7") (pinfunction "A4_7") (pintype "input"))
    )
    (net (code "87") (name "/XA5") (class "Default")
      (node (ref "U1") (pin "P120") (pinfunction "IO_L62N_VREF_0_P120") (pintype "bidirectional"))
      (node (ref "U3") (pin "16") (pinfunction "A5_16") (pintype "input"))
    )
    (net (code "88") (name "/XA6") (class "Default")
      (node (ref "U1") (pin "P118") (pinfunction "IO_L63N_SCP6_0_P118") (pintype "bidirectional"))
      (node (ref "U3") (pin "17") (pinfunction "A6_17") (pintype "input"))
    )
    (net (code "89") (name "/XA7") (class "Default")
      (node (ref "U1") (pin "P116") (pinfunction "IO_L64N_SCP4_0_P116") (pintype "bidirectional"))
      (node (ref "U3") (pin "18") (pinfunction "A7_18") (pintype "input"))
    )
    (net (code "90") (name "/XA8") (class "Default")
      (node (ref "U1") (pin "P114") (pinfunction "IO_L65N_SCP2_0_P114") (pintype "bidirectional"))
      (node (ref "U3") (pin "19") (pinfunction "A8_19") (pintype "input"))
    )
    (net (code "91") (name "/XA9") (class "Default")
      (node (ref "U1") (pin "P112") (pinfunction "IO_L66P_SCP1_0_P112") (pintype "bidirectional"))
      (node (ref "U3") (pin "20") (pinfunction "A9_20") (pintype "input"))
    )
    (net (code "92") (name "/XA10") (class "Default")
      (node (ref "U1") (pin "P104") (pinfunction "IO_L1N_VREF_1_P104") (pintype "bidirectional"))
      (node (ref "U3") (pin "26") (pinfunction "A10_26") (pintype "input"))
    )
    (net (code "93") (name "/XA11") (class "Default")
      (node (ref "U1") (pin "P102") (pinfunction "IO_L32P_1_P102") (pintype "bidirectional"))
      (node (ref "U3") (pin "27") (pinfunction "A11_27") (pintype "input"))
    )
    (net (code "94") (name "/XA12") (class "Default")
      (node (ref "U1") (pin "P101") (pinfunction "IO_L32N_1_P101") (pintype "bidirectional"))
      (node (ref "U3") (pin "28") (pinfunction "A12_28") (pintype "input"))
    )
    (net (code "95") (name "/XA13") (class "Default")
      (node (ref "U1") (pin "P100") (pinfunction "IO_L33P_1_P100") (pintype "bidirectional"))
      (node (ref "U3") (pin "29") (pinfunction "A13_29") (pintype "input"))
    )
    (net (code "96") (name "/XA14") (class "Default")
      (node (ref "U1") (pin "P111") (pinfunction "IO_L66N_SCP0_0_P111") (pintype "bidirectional"))
      (node (ref "U3") (pin "30") (pinfunction "A14_30") (pintype "input"))
    )
    (net (code "97") (name "/XA15") (class "Default")
      (node (ref "U1") (pin "P131") (pinfunction "IO_L35N_GCLK16_0_P131") (pintype "bidirectional"))
      (node (ref "U3") (pin "38") (pinfunction "A15_38") (pintype "input"))
    )
    (net (code "98") (name "/XA16") (class "Default")
      (node (ref "U1") (pin "P138") (pinfunction "IO_L4P_0_P138") (pintype "bidirectional"))
      (node (ref "U3") (pin "39") (pinfunction "A16_39") (pintype "input"))
    )
    (net (code "99") (name "/XA17") (class "Default")
      (node (ref "U1") (pin "P140") (pinfunction "IO_L3P_0_P140") (pintype "bidirectional"))
      (node (ref "U3") (pin "40") (pinfunction "A17_40") (pintype "input"))
    )
    (net (code "100") (name "/XA18") (class "Default")
      (node (ref "U1") (pin "P142") (pinfunction "IO_L2P_0_P142") (pintype "bidirectional"))
      (node (ref "U3") (pin "41") (pinfunction "A18/NC_41") (pintype "input"))
    )
    (net (code "101") (name "/XA19") (class "Default")
      (node (ref "U1") (pin "P105") (pinfunction "IO_L1P_1_P105") (pintype "bidirectional"))
      (node (ref "U3") (pin "25") (pinfunction "A19/NC_25") (pintype "input"))
    )
    (net (code "102") (name "/XA20") (class "Default")
      (node (ref "U1") (pin "P143") (pinfunction "IO_L1N_VREF_0_P143") (pintype "bidirectional"))
      (node (ref "U3") (pin "42") (pinfunction "A20/NC_42") (pintype "input"))
    )
    (net (code "103") (name "/XD0") (class "Default")
      (node (ref "U1") (pin "P132") (pinfunction "IO_L35P_GCLK17_0_P132") (pintype "bidirectional"))
      (node (ref "U3") (pin "9") (pinfunction "D0_9") (pintype "bidirectional"))
    )
    (net (code "104") (name "/XD1") (class "Default")
      (node (ref "U1") (pin "P127") (pinfunction "IO_L36P_GCLK15_0_P127") (pintype "bidirectional"))
      (node (ref "U3") (pin "10") (pinfunction "D1_10") (pintype "bidirectional"))
    )
    (net (code "105") (name "/XD2") (class "Default")
      (node (ref "U1") (pin "P124") (pinfunction "IO_L37P_GCLK13_0_P124") (pintype "bidirectional"))
      (node (ref "U3") (pin "13") (pinfunction "D2_13") (pintype "bidirectional"))
    )
    (net (code "106") (name "/XD3") (class "Default")
      (node (ref "U1") (pin "P123") (pinfunction "IO_L37N_GCLK12_0_P123") (pintype "bidirectional"))
      (node (ref "U3") (pin "14") (pinfunction "D3_14") (pintype "bidirectional"))
    )
    (net (code "107") (name "/XD4") (class "Default")
      (node (ref "U1") (pin "P115") (pinfunction "IO_L65P_SCP3_0_P115") (pintype "bidirectional"))
      (node (ref "U3") (pin "31") (pinfunction "D4_31") (pintype "bidirectional"))
    )
    (net (code "108") (name "/XD5") (class "Default")
      (node (ref "U1") (pin "P117") (pinfunction "IO_L64P_SCP5_0_P117") (pintype "bidirectional"))
      (node (ref "U3") (pin "32") (pinfunction "D5_32") (pintype "bidirectional"))
    )
    (net (code "109") (name "/XD6") (class "Default")
      (node (ref "U1") (pin "P119") (pinfunction "IO_L63P_SCP7_0_P119") (pintype "bidirectional"))
      (node (ref "U3") (pin "35") (pinfunction "D6_35") (pintype "bidirectional"))
    )
    (net (code "110") (name "/XD7") (class "Default")
      (node (ref "U1") (pin "P126") (pinfunction "IO_L36N_GCLK14_0_P126") (pintype "bidirectional"))
      (node (ref "U3") (pin "36") (pinfunction "D7_36") (pintype "bidirectional"))
    )
    (net (code "111") (name "1.2V") (class "Default")
      (node (ref "C10") (pin "2") (pinfunction "2_2") (pintype "passive"))
      (node (ref "C11") (pin "2") (pinfunction "2_2") (pintype "passive"))
      (node (ref "C12") (pin "2") (pinfunction "2_2") (pintype "passive"))
      (node (ref "C13") (pin "2") (pinfunction "2_2") (pintype "passive"))
      (node (ref "C9") (pin "2") (pinfunction "2_2") (pintype "passive"))
      (node (ref "L2") (pin "2") (pinfunction "2_2") (pintype "passive"))
      (node (ref "U1") (pin "P128") (pinfunction "VCCINT_P128") (pintype "input"))
      (node (ref "U1") (pin "P19") (pinfunction "VCCINT_P19") (pintype "input"))
      (node (ref "U1") (pin "P28") (pinfunction "VCCINT_P28") (pintype "input"))
      (node (ref "U1") (pin "P52") (pinfunction "VCCINT_P52") (pintype "input"))
      (node (ref "U1") (pin "P89") (pinfunction "VCCINT_P89") (pintype "input"))
    )
    (net (code "112") (name "3.3V") (class "Default")
      (node (ref "C14") (pin "2") (pinfunction "2_2") (pintype "passive"))
      (node (ref "C15") (pin "2") (pinfunction "2_2") (pintype "passive"))
      (node (ref "C16") (pin "2") (pinfunction "2_2") (pintype "passive"))
      (node (ref "C17") (pin "2") (pinfunction "2_2") (pintype "passive"))
      (node (ref "C18") (pin "2") (pinfunction "2_2") (pintype "passive"))
      (node (ref "C19") (pin "2") (pinfunction "2_2") (pintype "passive"))
      (node (ref "C20") (pin "2") (pinfunction "2_2") (pintype "passive"))
      (node (ref "C21") (pin "2") (pinfunction "2_2") (pintype "passive"))
      (node (ref "C22") (pin "2") (pinfunction "2_2") (pintype "passive"))
      (node (ref "C23") (pin "2") (pinfunction "2_2") (pintype "passive"))
      (node (ref "C24") (pin "2") (pinfunction "2_2") (pintype "passive"))
      (node (ref "C25") (pin "2") (pinfunction "2_2") (pintype "passive"))
      (node (ref "C26") (pin "1") (pinfunction "1_1") (pintype "passive"))
      (node (ref "C27") (pin "2") (pinfunction "2_2") (pintype "passive"))
      (node (ref "J11") (pin "1") (pinfunction "1_1") (pintype "passive"))
      (node (ref "J12") (pin "12") (pinfunction "12_12") (pintype "passive"))
      (node (ref "JTAG") (pin "1") (pinfunction "S_1") (pintype "passive"))
      (node (ref "L1") (pin "2") (pinfunction "2_2") (pintype "passive"))
      (node (ref "R24") (pin "2") (pinfunction "2_2") (pintype "passive"))
      (node (ref "R27") (pin "2") (pinfunction "2_2") (pintype "passive"))
      (node (ref "R30") (pin "1") (pinfunction "1_1") (pintype "passive"))
      (node (ref "R31") (pin "2") (pinfunction "2_2") (pintype "passive"))
      (node (ref "R32") (pin "2") (pinfunction "2_2") (pintype "passive"))
      (node (ref "RGB") (pin "4") (pinfunction "S_4") (pintype "passive"))
      (node (ref "SDCARD") (pin "4") (pinfunction "VDD_4") (pintype "power_in"))
      (node (ref "U1") (pin "P103") (pinfunction "VCCO_1_P103") (pintype "input"))
      (node (ref "U1") (pin "P122") (pinfunction "VCCO_0_P122") (pintype "input"))
      (node (ref "U1") (pin "P125") (pinfunction "VCCO_0_P125") (pintype "input"))
      (node (ref "U1") (pin "P129") (pinfunction "VCCAUX_P129") (pintype "input"))
      (node (ref "U1") (pin "P135") (pinfunction "VCCO_0_P135") (pintype "input"))
      (node (ref "U1") (pin "P18") (pinfunction "VCCO_3_P18") (pintype "input"))
      (node (ref "U1") (pin "P20") (pinfunction "VCCAUX_P20") (pintype "input"))
      (node (ref "U1") (pin "P31") (pinfunction "VCCO_3_P31") (pintype "input"))
      (node (ref "U1") (pin "P36") (pinfunction "VCCAUX_P36") (pintype "input"))
      (node (ref "U1") (pin "P4") (pinfunction "VCCO_3_P4") (pintype "input"))
      (node (ref "U1") (pin "P42") (pinfunction "VCCO_2_P42") (pintype "input"))
      (node (ref "U1") (pin "P53") (pinfunction "VCCAUX_P53") (pintype "input"))
      (node (ref "U1") (pin "P63") (pinfunction "VCCO_2_P63") (pintype "input"))
      (node (ref "U1") (pin "P69") (pinfunction "IO_L1N_M0_CMPMISO_2_P69") (pintype "bidirectional"))
      (node (ref "U1") (pin "P76") (pinfunction "VCCO_1_P76") (pintype "input"))
      (node (ref "U1") (pin "P86") (pinfunction "VCCO_1_P86") (pintype "input"))
      (node (ref "U1") (pin "P90") (pinfunction "VCCAUX_P90") (pintype "input"))
      (node (ref "U2") (pin "8") (pinfunction "VCC_8") (pintype "bidirectional"))
      (node (ref "U3") (pin "11") (pinfunction "VDD_11") (pintype "input"))
      (node (ref "U3") (pin "33") (pinfunction "VDD_33") (pintype "input"))
      (node (ref "U5") (pin "4") (pinfunction "VCC_4") (pintype "power_in"))
    )
    (net (code "113") (name "5V") (class "Default")
      (node (ref "C28") (pin "1") (pinfunction "1_1") (pintype "passive"))
      (node (ref "C30") (pin "1") (pinfunction "1_1") (pintype "passive"))
      (node (ref "C32") (pin "2") (pinfunction "2_2") (pintype "passive"))
      (node (ref "C33") (pin "2") (pinfunction "2_2") (pintype "passive"))
      (node (ref "J12") (pin "1") (pinfunction "1_1") (pintype "passive"))
      (node (ref "L3") (pin "2") (pinfunction "2_2") (pintype "passive"))
      (node (ref "PS/2") (pin "4") (pinfunction "4_4") (pintype "passive"))
      (node (ref "R5") (pin "1") (pinfunction "1_1") (pintype "passive"))
      (node (ref "R7") (pin "2") (pinfunction "2_2") (pintype "passive"))
      (node (ref "U4") (pin "14") (pinfunction "DPOS_14") (pintype "bidirectional"))
      (node (ref "U4") (pin "15") (pinfunction "VSYNC_15") (pintype "bidirectional"))
      (node (ref "U4") (pin "4") (pinfunction "APOS_4") (pintype "bidirectional"))
      (node (ref "U4") (pin "5") (pinfunction "CE_5") (pintype "bidirectional"))
      (node (ref "U6") (pin "3") (pinfunction "VIN_3") (pintype "input"))
      (node (ref "U7") (pin "3") (pinfunction "VIN_3") (pintype "input"))
    )
    (net (code "114") (name "GND") (class "Default")
      (node (ref "AUDIO") (pin "SLEEVE") (pinfunction "SLEEVE_SLEEVE") (pintype "bidirectional"))
      (node (ref "C1") (pin "2") (pinfunction "2_2") (pintype "passive"))
      (node (ref "C10") (pin "1") (pinfunction "1_1") (pintype "passive"))
      (node (ref "C11") (pin "1") (pinfunction "1_1") (pintype "passive"))
      (node (ref "C12") (pin "1") (pinfunction "1_1") (pintype "passive"))
      (node (ref "C13") (pin "1") (pinfunction "1_1") (pintype "passive"))
      (node (ref "C14") (pin "1") (pinfunction "1_1") (pintype "passive"))
      (node (ref "C15") (pin "1") (pinfunction "1_1") (pintype "passive"))
      (node (ref "C16") (pin "1") (pinfunction "1_1") (pintype "passive"))
      (node (ref "C17") (pin "1") (pinfunction "1_1") (pintype "passive"))
      (node (ref "C18") (pin "1") (pinfunction "1_1") (pintype "passive"))
      (node (ref "C19") (pin "1") (pinfunction "1_1") (pintype "passive"))
      (node (ref "C2") (pin "2") (pinfunction "2_2") (pintype "passive"))
      (node (ref "C20") (pin "1") (pinfunction "1_1") (pintype "passive"))
      (node (ref "C21") (pin "1") (pinfunction "1_1") (pintype "passive"))
      (node (ref "C22") (pin "1") (pinfunction "1_1") (pintype "passive"))
      (node (ref "C23") (pin "1") (pinfunction "1_1") (pintype "passive"))
      (node (ref "C24") (pin "1") (pinfunction "1_1") (pintype "passive"))
      (node (ref "C25") (pin "1") (pinfunction "1_1") (pintype "passive"))
      (node (ref "C26") (pin "2") (pinfunction "2_2") (pintype "passive"))
      (node (ref "C27") (pin "1") (pinfunction "1_1") (pintype "passive"))
      (node (ref "C28") (pin "2") (pinfunction "2_2") (pintype "passive"))
      (node (ref "C29") (pin "2") (pinfunction "2_2") (pintype "passive"))
      (node (ref "C3") (pin "2") (pinfunction "2_2") (pintype "passive"))
      (node (ref "C30") (pin "2") (pinfunction "2_2") (pintype "passive"))
      (node (ref "C31") (pin "2") (pinfunction "2_2") (pintype "passive"))
      (node (ref "C32") (pin "1") (pinfunction "1_1") (pintype "passive"))
      (node (ref "C33") (pin "1") (pinfunction "1_1") (pintype "passive"))
      (node (ref "C4") (pin "2") (pinfunction "2_2") (pintype "passive"))
      (node (ref "C9") (pin "1") (pinfunction "1_1") (pintype "passive"))
      (node (ref "CVBS") (pin "GND") (pinfunction "GND_GND") (pintype "passive"))
      (node (ref "D1") (pin "A") (pinfunction "A_A") (pintype "passive"))
      (node (ref "D2") (pin "C") (pinfunction "C_C") (pintype "passive"))
      (node (ref "D3") (pin "C") (pinfunction "C_C") (pintype "passive"))
      (node (ref "D4") (pin "C") (pinfunction "C_C") (pintype "passive"))
      (node (ref "D5") (pin "C") (pinfunction "C_C") (pintype "passive"))
      (node (ref "EAR") (pin "SLEEVE") (pinfunction "SLEEVE_SLEEVE") (pintype "bidirectional"))
      (node (ref "J10") (pin "12") (pinfunction "12_12") (pintype "passive"))
      (node (ref "J11") (pin "12") (pinfunction "12_12") (pintype "passive"))
      (node (ref "JOY") (pin "8") (pinfunction "8_8") (pintype "passive"))
      (node (ref "JTAG") (pin "2") (pinfunction "S_2") (pintype "passive"))
      (node (ref "PS/2") (pin "3") (pinfunction "3_3") (pintype "passive"))
      (node (ref "PWCON") (pin "1") (pinfunction "1_1") (pintype "passive"))
      (node (ref "PWUSB") (pin "5") (pinfunction "GND_5") (pintype "bidirectional"))
      (node (ref "R1") (pin "2") (pinfunction "2_2") (pintype "passive"))
      (node (ref "R2") (pin "2") (pinfunction "2_2") (pintype "passive"))
      (node (ref "R29") (pin "2") (pinfunction "2_2") (pintype "passive"))
      (node (ref "R3") (pin "2") (pinfunction "2_2") (pintype "passive"))
      (node (ref "RGB") (pin "1") (pinfunction "S_1") (pintype "passive"))
      (node (ref "RST") (pin "1") (pinfunction "1_1") (pintype "passive"))
      (node (ref "SDCARD") (pin "3") (pinfunction "VSS1_3") (pintype "power_in"))
      (node (ref "SDCARD") (pin "6") (pinfunction "VSS2_6") (pintype "power_in"))
      (node (ref "SDCARD") (pin "M1") (pinfunction "GND_M1") (pintype "power_in"))
      (node (ref "SDCARD") (pin "M2") (pinfunction "GND_M2") (pintype "power_in"))
      (node (ref "SDCARD") (pin "M3") (pinfunction "GND_M3") (pintype "power_in"))
      (node (ref "SDCARD") (pin "M4") (pinfunction "GND_M4") (pintype "power_in"))
      (node (ref "T1") (pin "2") (pinfunction "E_2") (pintype "passive"))
      (node (ref "U1") (pin "P108") (pinfunction "GND_P108") (pintype "power_in"))
      (node (ref "U1") (pin "P113") (pinfunction "GND_P113") (pintype "power_in"))
      (node (ref "U1") (pin "P13") (pinfunction "GND_P13") (pintype "power_in"))
      (node (ref "U1") (pin "P130") (pinfunction "GND_P130") (pintype "power_in"))
      (node (ref "U1") (pin "P136") (pinfunction "GND_P136") (pintype "power_in"))
      (node (ref "U1") (pin "P144") (pinfunction "IO_L1P_HSWAPEN_0_P144") (pintype "bidirectional"))
      (node (ref "U1") (pin "P25") (pinfunction "GND_P25") (pintype "power_in"))
      (node (ref "U1") (pin "P3") (pinfunction "GND_P3") (pintype "power_in"))
      (node (ref "U1") (pin "P49") (pinfunction "GND_P49") (pintype "power_in"))
      (node (ref "U1") (pin "P54") (pinfunction "GND_P54") (pintype "power_in"))
      (node (ref "U1") (pin "P60") (pinfunction "IO_L13P_M1_2_P60") (pintype "bidirectional"))
      (node (ref "U1") (pin "P68") (pinfunction "GND_P68") (pintype "power_in"))
      (node (ref "U1") (pin "P73") (pinfunction "SUSPEND_P73") (pintype "input"))
      (node (ref "U1") (pin "P77") (pinfunction "GND_P77") (pintype "power_in"))
      (node (ref "U1") (pin "P91") (pinfunction "GND_P91") (pintype "power_in"))
      (node (ref "U1") (pin "P96") (pinfunction "GND_P96") (pintype "power_in"))
      (node (ref "U2") (pin "4") (pinfunction "GND_4") (pintype "bidirectional"))
      (node (ref "U3") (pin "12") (pinfunction "VSS_12") (pintype "input"))
      (node (ref "U3") (pin "34") (pinfunction "VSS_34") (pintype "input"))
      (node (ref "U3") (pin "37") (pinfunction "~{OE}_37") (pintype "input"))
      (node (ref "U3") (pin "8") (pinfunction "~{CS}_8") (pintype "input"))
      (node (ref "U4") (pin "12") (pinfunction "YTRAP_12") (pintype "bidirectional"))
      (node (ref "U4") (pin "13") (pinfunction "DGND_13") (pintype "bidirectional"))
      (node (ref "U4") (pin "2") (pinfunction "AGND_2") (pintype "bidirectional"))
      (node (ref "U5") (pin "2") (pinfunction "GND_2") (pintype "power_in"))
      (node (ref "U6") (pin "1") (pinfunction "GND_1") (pintype "power_in"))
      (node (ref "U7") (pin "1") (pinfunction "GND_1") (pintype "power_in"))
    )
    (net (code "115") (name "Net-(C2-Pad1)") (class "Default")
      (node (ref "C2") (pin "1") (pinfunction "1_1") (pintype "passive"))
      (node (ref "C5") (pin "1") (pinfunction "1_1") (pintype "passive"))
      (node (ref "D1") (pin "C") (pinfunction "C_C") (pintype "passive"))
      (node (ref "R28") (pin "1") (pinfunction "1_1") (pintype "passive"))
    )
    (net (code "116") (name "Net-(C3-Pad1)") (class "Default")
      (node (ref "C3") (pin "1") (pinfunction "1_1") (pintype "passive"))
      (node (ref "C35") (pin "1") (pinfunction "1_1") (pintype "passive"))
      (node (ref "R23") (pin "1") (pinfunction "1_1") (pintype "passive"))
    )
    (net (code "117") (name "Net-(C5-Pad2)") (class "Default")
      (node (ref "C5") (pin "2") (pinfunction "2_2") (pintype "passive"))
      (node (ref "R15") (pin "2") (pinfunction "2_2") (pintype "passive"))
    )
    (net (code "118") (name "Net-(C34-Pad1)") (class "Default")
      (node (ref "C34") (pin "1") (pinfunction "1_1") (pintype "passive"))
      (node (ref "C4") (pin "1") (pinfunction "1_1") (pintype "passive"))
      (node (ref "R22") (pin "1") (pinfunction "1_1") (pintype "passive"))
    )
    (net (code "119") (name "Net-(C36-Pad-)") (class "Default")
      (node (ref "C36") (pin "-") (pinfunction "-_-") (pintype "passive"))
      (node (ref "R4") (pin "1") (pinfunction "1_1") (pintype "passive"))
    )
    (net (code "120") (name "Net-(CVBS-PadSIG)") (class "Default")
      (node (ref "CVBS") (pin "SIG") (pinfunction "SIG_SIG") (pintype "passive"))
      (node (ref "R4") (pin "2") (pinfunction "2_2") (pintype "passive"))
    )
    (net (code "121") (name "Net-(D2-PadA)") (class "Default")
      (node (ref "D2") (pin "A") (pinfunction "A_A") (pintype "passive"))
      (node (ref "R25") (pin "2") (pinfunction "2_2") (pintype "passive"))
      (node (ref "Y1") (pin "1") (pinfunction "1_1") (pintype "passive"))
    )
    (net (code "122") (name "Net-(D3-PadA)") (class "Default")
      (node (ref "D3") (pin "A") (pinfunction "A_A") (pintype "passive"))
      (node (ref "R26") (pin "1") (pinfunction "1_1") (pintype "passive"))
      (node (ref "Y2") (pin "1") (pinfunction "1_1") (pintype "passive"))
    )
    (net (code "123") (name "Net-(D4-PadA)") (class "Default")
      (node (ref "D4") (pin "A") (pinfunction "A_A") (pintype "passive"))
      (node (ref "R6") (pin "1") (pinfunction "1_1") (pintype "passive"))
    )
    (net (code "124") (name "Net-(D5-PadA)") (class "Default")
      (node (ref "D5") (pin "A") (pinfunction "A_A") (pintype "passive"))
      (node (ref "R7") (pin "1") (pinfunction "1_1") (pintype "passive"))
    )
    (net (code "125") (name "Net-(EAR-LEFT)") (class "Default")
      (node (ref "EAR") (pin "TIP") (pinfunction "LEFT_TIP") (pintype "bidirectional"))
      (node (ref "R15") (pin "1") (pinfunction "1_1") (pintype "passive"))
      (node (ref "R29") (pin "1") (pinfunction "1_1") (pintype "passive"))
    )
    (net (code "126") (name "Net-(J16-Pad4)") (class "Default")
      (node (ref "J16") (pin "4") (pinfunction "4_4") (pintype "passive"))
      (node (ref "R5") (pin "2") (pinfunction "2_2") (pintype "passive"))
    )
    (net (code "127") (name "Net-(L3-Pad1)") (class "Default")
      (node (ref "L3") (pin "1") (pinfunction "1_1") (pintype "passive"))
      (node (ref "SW") (pin "1") (pinfunction "1_1") (pintype "passive"))
    )
    (net (code "128") (name "Net-(PS/2-Pad1)") (class "Default")
      (node (ref "PS/2") (pin "1") (pinfunction "1_1") (pintype "passive"))
      (node (ref "R8") (pin "1") (pinfunction "1_1") (pintype "passive"))
    )
    (net (code "129") (name "Net-(PS/2-Pad2)") (class "Default")
      (node (ref "PS/2") (pin "2") (pinfunction "2_2") (pintype "passive"))
      (node (ref "R9") (pin "1") (pinfunction "1_1") (pintype "passive"))
    )
    (net (code "130") (name "Net-(PS/2-Pad5)") (class "Default")
      (node (ref "PS/2") (pin "5") (pinfunction "5_5") (pintype "passive"))
      (node (ref "R10") (pin "1") (pinfunction "1_1") (pintype "passive"))
    )
    (net (code "131") (name "Net-(PS/2-Pad6)") (class "Default")
      (node (ref "PS/2") (pin "6") (pinfunction "6_6") (pintype "passive"))
      (node (ref "R11") (pin "1") (pinfunction "1_1") (pintype "passive"))
    )
    (net (code "132") (name "Net-(PWUSB-VCC)") (class "Default")
      (node (ref "PWCON") (pin "2") (pinfunction "2_2") (pintype "passive"))
      (node (ref "PWUSB") (pin "1") (pinfunction "VCC_1") (pintype "bidirectional"))
      (node (ref "SW") (pin "2") (pinfunction "2_2") (pintype "passive"))
    )
    (net (code "133") (name "Net-(SDCARD-DAT1)") (class "Default")
      (node (ref "R31") (pin "1") (pinfunction "1_1") (pintype "passive"))
      (node (ref "SDCARD") (pin "8") (pinfunction "DAT1_8") (pintype "bidirectional"))
    )
    (net (code "134") (name "Net-(SDCARD-DAT2)") (class "Default")
      (node (ref "R32") (pin "1") (pinfunction "1_1") (pintype "passive"))
      (node (ref "SDCARD") (pin "9") (pinfunction "DAT2_9") (pintype "bidirectional"))
    )
    (net (code "135") (name "Net-(T1-B)") (class "Default")
      (node (ref "R28") (pin "2") (pinfunction "2_2") (pintype "passive"))
      (node (ref "T1") (pin "1") (pinfunction "B_1") (pintype "passive"))
    )
    (net (code "136") (name "Net-(U1C-PROGRAM_B_2)") (class "Default")
      (node (ref "R24") (pin "1") (pinfunction "1_1") (pintype "passive"))
      (node (ref "RST") (pin "2") (pinfunction "2_2") (pintype "passive"))
      (node (ref "U1") (pin "P37") (pinfunction "PROGRAM_B_2_P37") (pintype "input"))
    )
    (net (code "137") (name "Net-(U4-4FSC)") (class "Default")
      (node (ref "C1") (pin "1") (pinfunction "1_1") (pintype "passive"))
      (node (ref "U4") (pin "3") (pinfunction "4FSC_3") (pintype "bidirectional"))
      (node (ref "Y1") (pin "2") (pinfunction "2_2") (pintype "passive"))
      (node (ref "Y2") (pin "2") (pinfunction "2_2") (pintype "passive"))
    )
    (net (code "138") (name "Net-(U4-BIN)") (class "Default")
      (node (ref "C8") (pin "1") (pinfunction "1_1") (pintype "passive"))
      (node (ref "U4") (pin "8") (pinfunction "BIN_8") (pintype "bidirectional"))
    )
    (net (code "139") (name "Net-(U4-COMP)") (class "Default")
      (node (ref "C36") (pin "+") (pinfunction "+_+") (pintype "passive"))
      (node (ref "U4") (pin "10") (pinfunction "COMP_10") (pintype "bidirectional"))
    )
    (net (code "140") (name "Net-(U4-GIN)") (class "Default")
      (node (ref "C7") (pin "1") (pinfunction "1_1") (pintype "passive"))
      (node (ref "U4") (pin "7") (pinfunction "GIN_7") (pintype "bidirectional"))
    )
    (net (code "141") (name "Net-(U4-RIN)") (class "Default")
      (node (ref "C6") (pin "1") (pinfunction "1_1") (pintype "passive"))
      (node (ref "U4") (pin "6") (pinfunction "RIN_6") (pintype "bidirectional"))
    )
    (net (code "142") (name "Net-(U6-VOUT)") (class "Default")
      (node (ref "C29") (pin "1") (pinfunction "1_1") (pintype "passive"))
      (node (ref "L1") (pin "1") (pinfunction "1_1") (pintype "passive"))
      (node (ref "U6") (pin "2") (pinfunction "VOUT_2") (pintype "output"))
    )
    (net (code "143") (name "Net-(U7-VOUT)") (class "Default")
      (node (ref "C31") (pin "1") (pinfunction "1_1") (pintype "passive"))
      (node (ref "L2") (pin "1") (pinfunction "1_1") (pintype "passive"))
      (node (ref "U7") (pin "2") (pinfunction "VOUT_2") (pintype "output"))
    )
    (net (code "144") (name "unconnected-(EAR-RIGHT-PadRING)") (class "Default")
      (node (ref "EAR") (pin "RING") (pinfunction "RIGHT_RING") (pintype "bidirectional"))
    )
    (net (code "145") (name "unconnected-(J10-Pad11)") (class "Default")
      (node (ref "J10") (pin "11") (pinfunction "11_11") (pintype "passive"))
    )
    (net (code "146") (name "unconnected-(PWUSB-D+-Pad3)") (class "Default")
      (node (ref "PWUSB") (pin "3") (pinfunction "D+_3") (pintype "bidirectional"))
    )
    (net (code "147") (name "unconnected-(PWUSB-D--Pad2)") (class "Default")
      (node (ref "PWUSB") (pin "2") (pinfunction "D-_2") (pintype "bidirectional"))
    )
    (net (code "148") (name "unconnected-(PWUSB-ID-Pad4)") (class "Default")
      (node (ref "PWUSB") (pin "4") (pinfunction "ID_4") (pintype "bidirectional"))
    )
    (net (code "149") (name "unconnected-(PWUSB-SHIELD-Pad6)") (class "Default")
      (node (ref "PWUSB") (pin "6") (pinfunction "SHIELD_6") (pintype "bidirectional"))
    )
    (net (code "150") (name "unconnected-(SDCARD-CDI#-Pad10)") (class "Default")
      (node (ref "SDCARD") (pin "10") (pinfunction "CDI#_10") (pintype "output"))
    )
    (net (code "151") (name "unconnected-(SDCARD-WP-Pad11)") (class "Default")
      (node (ref "SDCARD") (pin "11") (pinfunction "WP_11") (pintype "output"))
    )
    (net (code "152") (name "unconnected-(U1C-CMPCS_B_2-PadP72)") (class "Default")
      (node (ref "U1") (pin "P72") (pinfunction "CMPCS_B_2_P72") (pintype "bidirectional"))
    )
    (net (code "153") (name "unconnected-(U1C-DONE_2-PadP71)") (class "Default")
      (node (ref "U1") (pin "P71") (pinfunction "DONE_2_P71") (pintype "bidirectional"))
    )
    (net (code "154") (name "unconnected-(U4-CRMA-Pad9)") (class "Default")
      (node (ref "U4") (pin "9") (pinfunction "CRMA_9") (pintype "bidirectional"))
    )
    (net (code "155") (name "unconnected-(U4-LUMA-Pad11)") (class "Default")
      (node (ref "U4") (pin "11") (pinfunction "LUMA_11") (pintype "bidirectional"))
    )
    (net (code "156") (name "unconnected-(U5-E{slash}D-Pad1)") (class "Default")
      (node (ref "U5") (pin "1") (pinfunction "E/D_1") (pintype "input"))
    )
  )
)
